# 2022.net
KiCad netlist of a schematic drawn in EAGLE
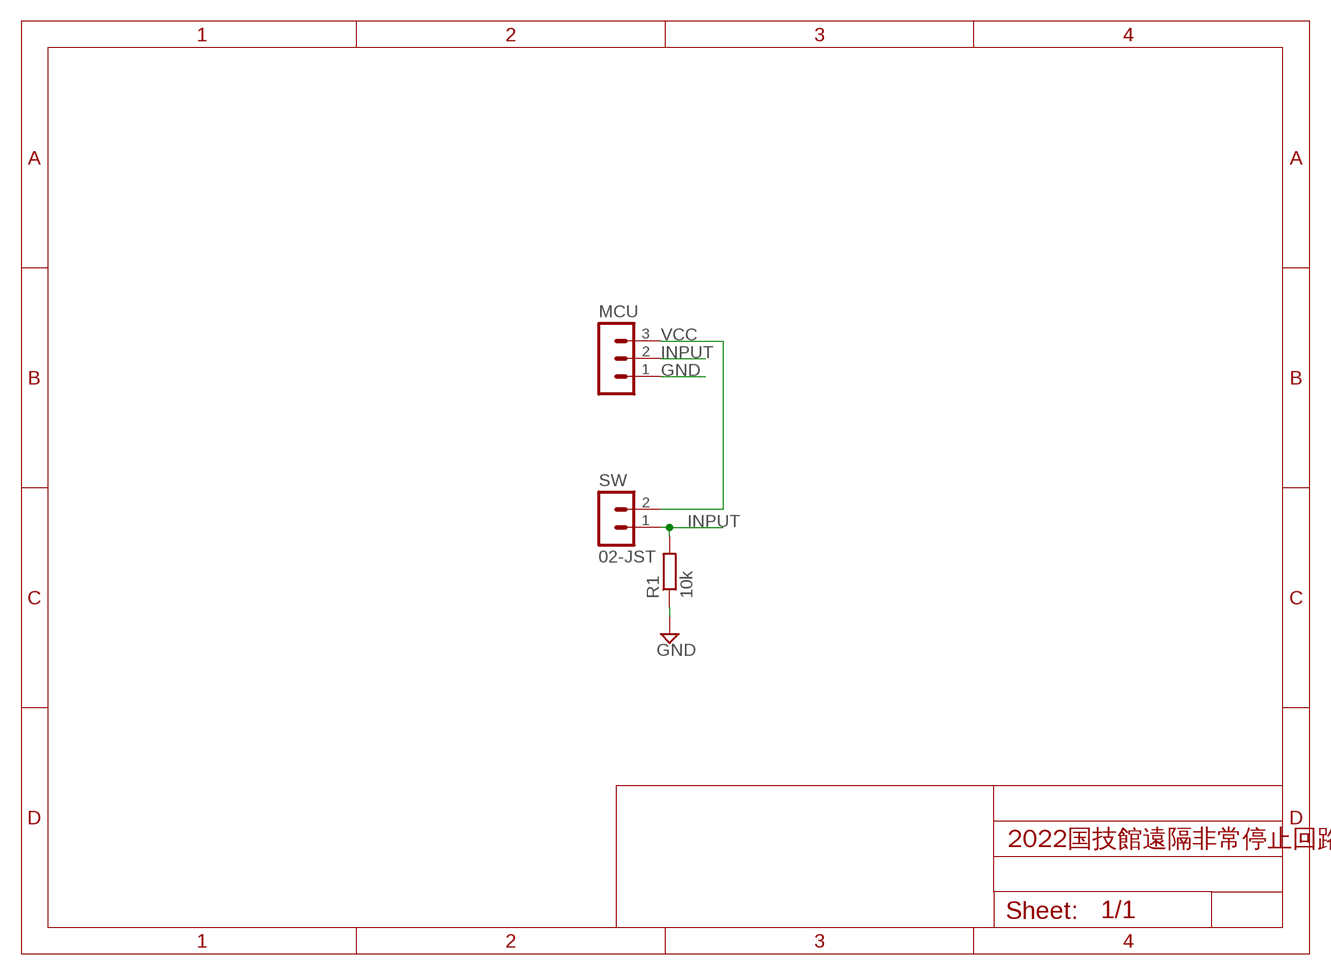
[diagram p0: schematic, sheet 1]

(export (version "E")
  (design (tool "Eeschema 10.0.6"))
  (components
    (comp (ref "MCU")
      (value "03-JST")
      (footprint "eagle-import:B3B-XH")
      (libsource (lib "eagle-import") (part "03-JST"))
    )
    (comp (ref "R1")
      (value "10k")
      (footprint "eagle-import:0204_7")
      (libsource (lib "eagle-import") (part "R-EU_0204/7"))
    )
    (comp (ref "SW")
      (value "02-JST")
      (footprint "eagle-import:B2B-XH")
      (libsource (lib "eagle-import") (part "02-JST"))
    )
  )
  (nets
    (net (code "1") (name "/INPUT") (class "Default")
      (node (ref "MCU") (pin "2") (pinfunction "2_2") (pintype "passive"))
      (node (ref "R1") (pin "2") (pinfunction "2_2") (pintype "passive"))
      (node (ref "SW") (pin "1") (pinfunction "1_1") (pintype "passive"))
    )
    (net (code "2") (name "/VCC") (class "Default")
      (node (ref "MCU") (pin "3") (pinfunction "3_3") (pintype "passive"))
      (node (ref "SW") (pin "2") (pinfunction "2_2") (pintype "passive"))
    )
    (net (code "3") (name "GND") (class "Default")
      (node (ref "MCU") (pin "1") (pinfunction "1_1") (pintype "passive"))
      (node (ref "R1") (pin "1") (pinfunction "1_1") (pintype "passive"))
    )
  )
)
